# DAPLink.net
KiCad netlist of a schematic drawn in Altium Designer
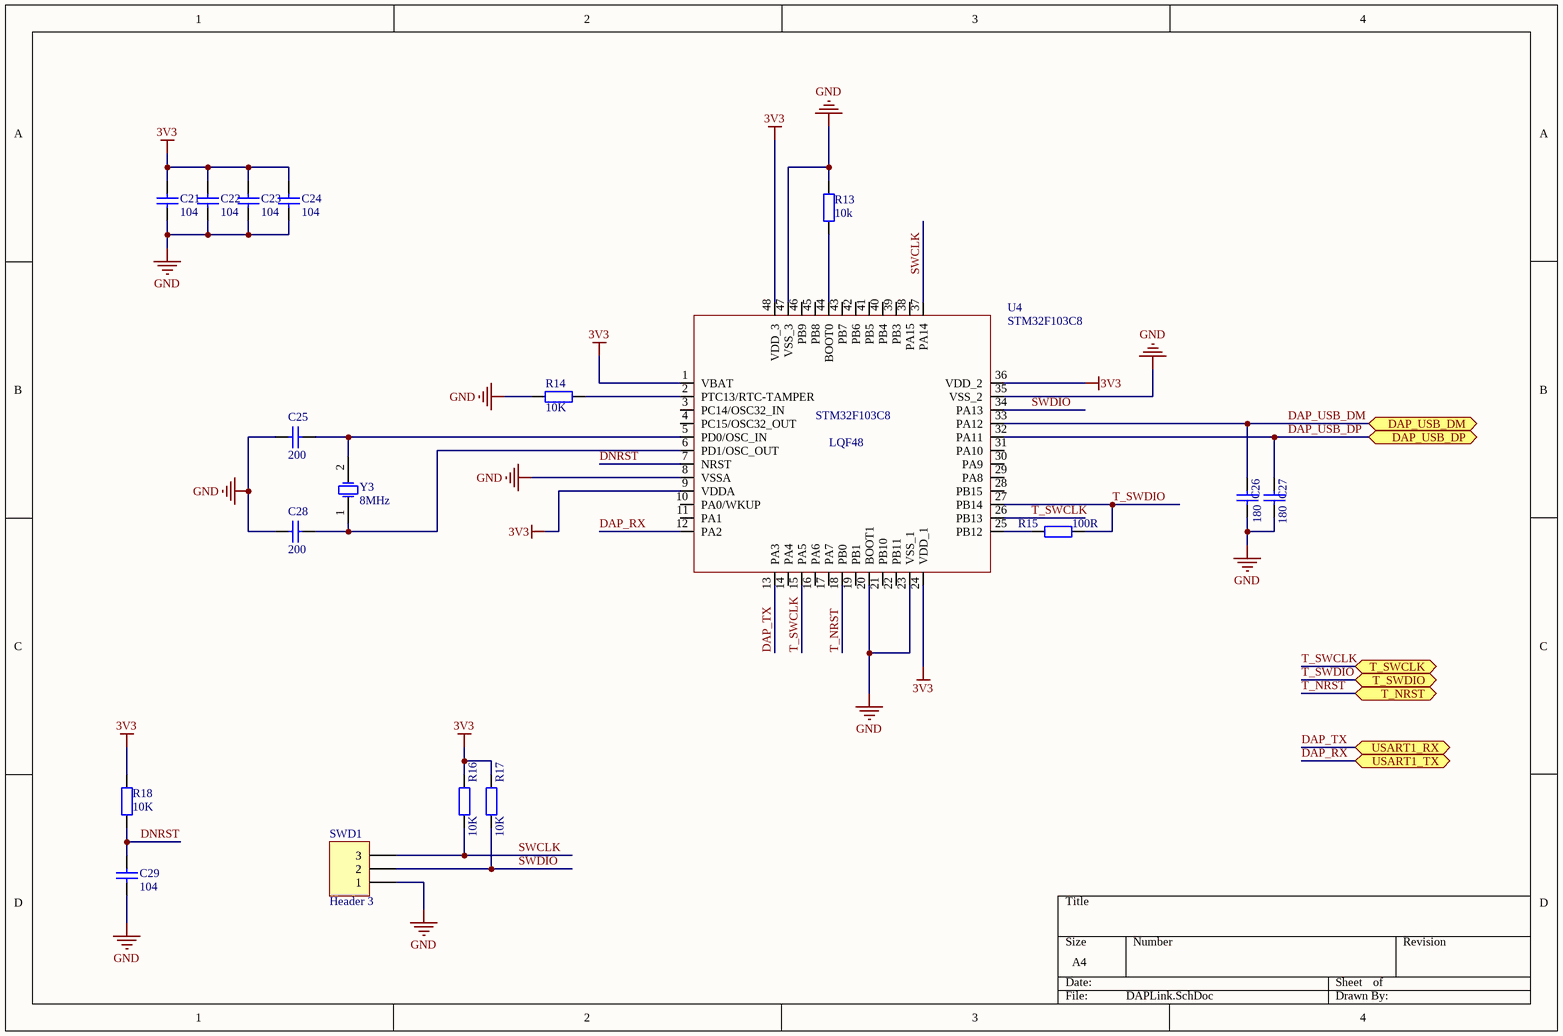
[diagram p0: DAPLink.SchDoc]

(export (version "E")
  (design (tool "Eeschema 10.0.6"))
  (components
    (comp (ref "C21")
      (value "104")
      (footprint "C_SOP_0603")
      (description "电容_无极性")
      (libsource (lib "lib-base") (part "Cap"))
    )
    (comp (ref "C22")
      (value "104")
      (footprint "C_SOP_0603")
      (description "电容_无极性")
      (libsource (lib "lib-base") (part "Cap"))
    )
    (comp (ref "C23")
      (value "104")
      (footprint "C_SOP_0603")
      (description "电容_无极性")
      (libsource (lib "lib-base") (part "Cap"))
    )
    (comp (ref "C24")
      (value "104")
      (footprint "C_SOP_0603")
      (description "电容_无极性")
      (libsource (lib "lib-base") (part "Cap"))
    )
    (comp (ref "C25")
      (value "200")
      (footprint "C_SOP_0603")
      (description "电容_无极性")
      (libsource (lib "lib-base") (part "Cap"))
    )
    (comp (ref "C26")
      (value "180")
      (footprint "C_SOP_0603")
      (description "电容_无极性")
      (libsource (lib "lib-base") (part "Cap"))
    )
    (comp (ref "C27")
      (value "180")
      (footprint "C_SOP_0603")
      (description "电容_无极性")
      (libsource (lib "lib-base") (part "Cap"))
    )
    (comp (ref "C28")
      (value "200")
      (footprint "C_SOP_0603")
      (description "电容_无极性")
      (libsource (lib "lib-base") (part "Cap"))
    )
    (comp (ref "C29")
      (value "104")
      (footprint "C_SOP_0603")
      (description "电容_无极性")
      (libsource (lib "lib-base") (part "Cap"))
    )
    (comp (ref "R13")
      (value "10k")
      (footprint "R_SMD_0603")
      (description "电阻")
      (libsource (lib "") (part "Res_1"))
    )
    (comp (ref "R14")
      (value "10K")
      (footprint "R_SMD_0603")
      (description "电阻")
      (libsource (lib "lib-base") (part "Res"))
    )
    (comp (ref "R15")
      (value "100R")
      (footprint "R_SMD_0603")
      (description "电阻")
      (libsource (lib "lib-base") (part "Res"))
    )
    (comp (ref "R16")
      (value "10K")
      (footprint "R_SMD_0603")
      (description "电阻")
      (libsource (lib "") (part "Res_1"))
    )
    (comp (ref "R17")
      (value "10K")
      (footprint "R_SMD_0603")
      (description "电阻")
      (libsource (lib "") (part "Res_1"))
    )
    (comp (ref "R18")
      (value "10K")
      (footprint "R_SMD_0603")
      (description "电阻")
      (libsource (lib "") (part "Res_1"))
    )
    (comp (ref "SWD1")
      (value "Header 3")
      (footprint "HDR1X3")
      (description "Header, 3-Pin")
      (fields (field (name "PUBLISHER") "Altium Limited"))
      (libsource (lib "Miscellaneous Connectors") (part "Header 3"))
    )
    (comp (ref "U4")
      (value "STM32F103C8")
      (footprint "LQFP_48_7X7")
      (description "ST-MCU")
      (libsource (lib "lib-ic") (part "STM32F103C8"))
    )
    (comp (ref "Y3") (value "8MHz") (footprint "XTAL_SMD_49S") (libsource (lib "DG") (part "XTAL_SMD")))
  )
  (nets
    (net (code "1") (name "/DAP_RX") (class "Default")
      (node (ref "U4") (pin "12") (pinfunction "PA2_12") (pintype "passive"))
    )
    (net (code "2") (name "/DAP_TX") (class "Default")
      (node (ref "U4") (pin "13") (pinfunction "PA3_13") (pintype "passive"))
    )
    (net (code "3") (name "/DAP_USB_DM") (class "Default")
      (node (ref "C26") (pin "2") (pinfunction "2_2") (pintype "passive"))
      (node (ref "U4") (pin "33") (pinfunction "PA12_33") (pintype "passive"))
    )
    (net (code "4") (name "/DAP_USB_DP") (class "Default")
      (node (ref "C27") (pin "2") (pinfunction "2_2") (pintype "passive"))
      (node (ref "U4") (pin "32") (pinfunction "PA11_32") (pintype "passive"))
    )
    (net (code "5") (name "/DNRST") (class "Default")
      (node (ref "C29") (pin "2") (pinfunction "2_2") (pintype "passive"))
      (node (ref "R18") (pin "1") (pinfunction "1_1") (pintype "passive"))
      (node (ref "U4") (pin "7") (pinfunction "NRST_7") (pintype "passive"))
    )
    (net (code "6") (name "/SWCLK") (class "Default")
      (node (ref "R16") (pin "1") (pinfunction "1_1") (pintype "passive"))
      (node (ref "SWD1") (pin "3") (pinfunction "3_3") (pintype "passive"))
      (node (ref "U4") (pin "37") (pinfunction "PA14_37") (pintype "passive"))
    )
    (net (code "7") (name "/SWDIO") (class "Default")
      (node (ref "R17") (pin "1") (pinfunction "1_1") (pintype "passive"))
      (node (ref "SWD1") (pin "2") (pinfunction "2_2") (pintype "passive"))
      (node (ref "U4") (pin "34") (pinfunction "PA13_34") (pintype "passive"))
    )
    (net (code "8") (name "/T_NRST") (class "Default")
      (node (ref "U4") (pin "18") (pinfunction "PB0_18") (pintype "passive"))
    )
    (net (code "9") (name "/T_SWCLK") (class "Default")
      (node (ref "U4") (pin "15") (pinfunction "PA5_15") (pintype "passive"))
      (node (ref "U4") (pin "26") (pinfunction "PB13_26") (pintype "passive"))
    )
    (net (code "10") (name "/T_SWDIO") (class "Default")
      (node (ref "R15") (pin "2") (pinfunction "2_2") (pintype "passive"))
      (node (ref "U4") (pin "27") (pinfunction "PB14_27") (pintype "passive"))
    )
    (net (code "11") (name "3V3") (class "Default")
      (node (ref "C21") (pin "2") (pinfunction "2_2") (pintype "passive"))
      (node (ref "C22") (pin "2") (pinfunction "2_2") (pintype "passive"))
      (node (ref "C23") (pin "2") (pinfunction "2_2") (pintype "passive"))
      (node (ref "C24") (pin "2") (pinfunction "2_2") (pintype "passive"))
      (node (ref "R16") (pin "2") (pinfunction "2_2") (pintype "passive"))
      (node (ref "R17") (pin "2") (pinfunction "2_2") (pintype "passive"))
      (node (ref "R18") (pin "2") (pinfunction "2_2") (pintype "passive"))
      (node (ref "U4") (pin "1") (pinfunction "VBAT_1") (pintype "passive"))
      (node (ref "U4") (pin "24") (pinfunction "VDD_1_24") (pintype "passive"))
      (node (ref "U4") (pin "36") (pinfunction "VDD_2_36") (pintype "passive"))
      (node (ref "U4") (pin "48") (pinfunction "VDD_3_48") (pintype "passive"))
      (node (ref "U4") (pin "9") (pinfunction "VDDA_9") (pintype "passive"))
    )
    (net (code "12") (name "GND") (class "Default")
      (node (ref "C21") (pin "1") (pinfunction "1_1") (pintype "passive"))
      (node (ref "C22") (pin "1") (pinfunction "1_1") (pintype "passive"))
      (node (ref "C23") (pin "1") (pinfunction "1_1") (pintype "passive"))
      (node (ref "C24") (pin "1") (pinfunction "1_1") (pintype "passive"))
      (node (ref "C25") (pin "1") (pinfunction "1_1") (pintype "passive"))
      (node (ref "C26") (pin "1") (pinfunction "1_1") (pintype "passive"))
      (node (ref "C27") (pin "1") (pinfunction "1_1") (pintype "passive"))
      (node (ref "C28") (pin "1") (pinfunction "1_1") (pintype "passive"))
      (node (ref "C29") (pin "1") (pinfunction "1_1") (pintype "passive"))
      (node (ref "R13") (pin "2") (pinfunction "2_2") (pintype "passive"))
      (node (ref "R14") (pin "1") (pinfunction "1_1") (pintype "passive"))
      (node (ref "SWD1") (pin "1") (pinfunction "1_1") (pintype "passive"))
      (node (ref "U4") (pin "20") (pinfunction "BOOT1_20") (pintype "passive"))
      (node (ref "U4") (pin "23") (pinfunction "VSS_1_23") (pintype "passive"))
      (node (ref "U4") (pin "35") (pinfunction "VSS_2_35") (pintype "passive"))
      (node (ref "U4") (pin "47") (pinfunction "VSS_3_47") (pintype "passive"))
      (node (ref "U4") (pin "8") (pinfunction "VSSA_8") (pintype "passive"))
    )
    (net (code "13") (name "Net-(U4-BOOT0)") (class "Default")
      (node (ref "R13") (pin "1") (pinfunction "1_1") (pintype "passive"))
      (node (ref "U4") (pin "44") (pinfunction "BOOT0_44") (pintype "passive"))
    )
    (net (code "14") (name "Net-(U4-PB12)") (class "Default")
      (node (ref "R15") (pin "1") (pinfunction "1_1") (pintype "passive"))
      (node (ref "U4") (pin "25") (pinfunction "PB12_25") (pintype "passive"))
    )
    (net (code "15") (name "Net-(U4-PD0{slash}OSC_IN)") (class "Default")
      (node (ref "C25") (pin "2") (pinfunction "2_2") (pintype "passive"))
      (node (ref "U4") (pin "5") (pinfunction "PD0/OSC_IN_5") (pintype "passive"))
      (node (ref "Y3") (pin "2") (pinfunction "OSC2_2") (pintype "passive"))
    )
    (net (code "16") (name "Net-(U4-PD1{slash}OSC_OUT)") (class "Default")
      (node (ref "C28") (pin "2") (pinfunction "2_2") (pintype "passive"))
      (node (ref "U4") (pin "6") (pinfunction "PD1/OSC_OUT_6") (pintype "passive"))
      (node (ref "Y3") (pin "1") (pinfunction "OSC1_1") (pintype "passive"))
    )
    (net (code "17") (name "Net-(U4-PTC13{slash}RTC-TAMPER)") (class "Default")
      (node (ref "R14") (pin "2") (pinfunction "2_2") (pintype "passive"))
      (node (ref "U4") (pin "2") (pinfunction "PTC13/RTC-TAMPER_2") (pintype "passive"))
    )
    (net (code "18") (name "unconnected-(U4-PA0{slash}WKUP-Pad10)") (class "Default")
      (node (ref "U4") (pin "10") (pinfunction "PA0/WKUP_10") (pintype "passive"))
    )
    (net (code "19") (name "unconnected-(U4-PA1-Pad11)") (class "Default")
      (node (ref "U4") (pin "11") (pinfunction "PA1_11") (pintype "passive"))
    )
    (net (code "20") (name "unconnected-(U4-PA4-Pad14)") (class "Default")
      (node (ref "U4") (pin "14") (pinfunction "PA4_14") (pintype "passive"))
    )
    (net (code "21") (name "unconnected-(U4-PA6-Pad16)") (class "Default")
      (node (ref "U4") (pin "16") (pinfunction "PA6_16") (pintype "passive"))
    )
    (net (code "22") (name "unconnected-(U4-PA7-Pad17)") (class "Default")
      (node (ref "U4") (pin "17") (pinfunction "PA7_17") (pintype "passive"))
    )
    (net (code "23") (name "unconnected-(U4-PA8-Pad29)") (class "Default")
      (node (ref "U4") (pin "29") (pinfunction "PA8_29") (pintype "passive"))
    )
    (net (code "24") (name "unconnected-(U4-PA9-Pad30)") (class "Default")
      (node (ref "U4") (pin "30") (pinfunction "PA9_30") (pintype "passive"))
    )
    (net (code "25") (name "unconnected-(U4-PA10-Pad31)") (class "Default")
      (node (ref "U4") (pin "31") (pinfunction "PA10_31") (pintype "passive"))
    )
    (net (code "26") (name "unconnected-(U4-PA15-Pad38)") (class "Default")
      (node (ref "U4") (pin "38") (pinfunction "PA15_38") (pintype "passive"))
    )
    (net (code "27") (name "unconnected-(U4-PB1-Pad19)") (class "Default")
      (node (ref "U4") (pin "19") (pinfunction "PB1_19") (pintype "passive"))
    )
    (net (code "28") (name "unconnected-(U4-PB3-Pad39)") (class "Default")
      (node (ref "U4") (pin "39") (pinfunction "PB3_39") (pintype "passive"))
    )
    (net (code "29") (name "unconnected-(U4-PB4-Pad40)") (class "Default")
      (node (ref "U4") (pin "40") (pinfunction "PB4_40") (pintype "passive"))
    )
    (net (code "30") (name "unconnected-(U4-PB5-Pad41)") (class "Default")
      (node (ref "U4") (pin "41") (pinfunction "PB5_41") (pintype "passive"))
    )
    (net (code "31") (name "unconnected-(U4-PB6-Pad42)") (class "Default")
      (node (ref "U4") (pin "42") (pinfunction "PB6_42") (pintype "passive"))
    )
    (net (code "32") (name "unconnected-(U4-PB7-Pad43)") (class "Default")
      (node (ref "U4") (pin "43") (pinfunction "PB7_43") (pintype "passive"))
    )
    (net (code "33") (name "unconnected-(U4-PB8-Pad45)") (class "Default")
      (node (ref "U4") (pin "45") (pinfunction "PB8_45") (pintype "passive"))
    )
    (net (code "34") (name "unconnected-(U4-PB9-Pad46)") (class "Default")
      (node (ref "U4") (pin "46") (pinfunction "PB9_46") (pintype "passive"))
    )
    (net (code "35") (name "unconnected-(U4-PB10-Pad21)") (class "Default")
      (node (ref "U4") (pin "21") (pinfunction "PB10_21") (pintype "passive"))
    )
    (net (code "36") (name "unconnected-(U4-PB11-Pad22)") (class "Default")
      (node (ref "U4") (pin "22") (pinfunction "PB11_22") (pintype "passive"))
    )
    (net (code "37") (name "unconnected-(U4-PB15-Pad28)") (class "Default")
      (node (ref "U4") (pin "28") (pinfunction "PB15_28") (pintype "passive"))
    )
    (net (code "38") (name "unconnected-(U4-PC14{slash}OSC32_IN-Pad3)") (class "Default")
      (node (ref "U4") (pin "3") (pinfunction "PC14/OSC32_IN_3") (pintype "passive"))
    )
    (net (code "39") (name "unconnected-(U4-PC15{slash}OSC32_OUT-Pad4)") (class "Default")
      (node (ref "U4") (pin "4") (pinfunction "PC15/OSC32_OUT_4") (pintype "passive"))
    )
  )
)
